# SDCARD.net
KiCad netlist of a schematic drawn in Altium Designer
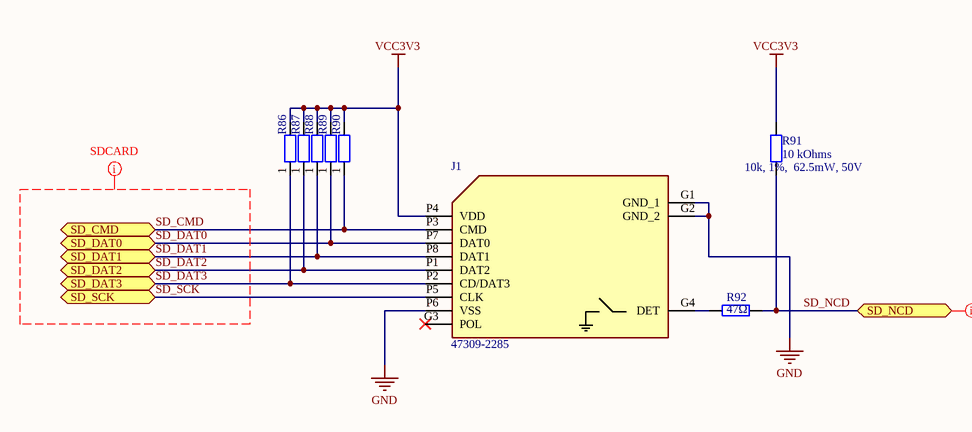
[diagram p0: SDCARD.SchDoc]

(export (version "E")
  (design (tool "Eeschema 10.0.6"))
  (components
    (comp (ref "J1")
      (value "47309-2285")
      (footprint "PCB1:473092285")
      (description "1.10mm Pitch microSD Card Header with Detect Pin Height 2.85mm Lead-Free Gold (Au) Plated 0.762")
      (fields (field (name "MOUSER PART NUMBER") "538-47309-2285") (field (name "MANUFACTURER") "Molex"))
      (libsource (lib "HamedLib") (part "47309-2285"))
    )
    (comp (ref "R86")
      (value "100 kOhms")
      (footprint "RES0402i")
      (description "0402, 100k, 1%, 62.5mW, 50V")
      (fields (field (name "PART NUMBER") "CR0402-FX-1003GLF") (field (name "VOLTAGE") "50 V"))
      (libsource (lib "AmpherLib") (part "Res_100K_1%_0402"))
    )
    (comp (ref "R87")
      (value "100 kOhms")
      (footprint "RES0402i")
      (description "0402, 100k, 1%, 62.5mW, 50V")
      (fields (field (name "PART NUMBER") "CR0402-FX-1003GLF") (field (name "VOLTAGE") "50 V"))
      (libsource (lib "AmpherLib") (part "Res_100K_1%_0402"))
    )
    (comp (ref "R88")
      (value "100 kOhms")
      (footprint "RES0402i")
      (description "0402, 100k, 1%, 62.5mW, 50V")
      (fields (field (name "PART NUMBER") "CR0402-FX-1003GLF") (field (name "VOLTAGE") "50 V"))
      (libsource (lib "AmpherLib") (part "Res_100K_1%_0402"))
    )
    (comp (ref "R89")
      (value "100 kOhms")
      (footprint "RES0402i")
      (description "0402, 100k, 1%, 62.5mW, 50V")
      (fields (field (name "PART NUMBER") "CR0402-FX-1003GLF") (field (name "VOLTAGE") "50 V"))
      (libsource (lib "AmpherLib") (part "Res_100K_1%_0402"))
    )
    (comp (ref "R90")
      (value "100 kOhms")
      (footprint "RES0402i")
      (description "0402, 100k, 1%, 62.5mW, 50V")
      (fields (field (name "PART NUMBER") "CR0402-FX-1003GLF") (field (name "VOLTAGE") "50 V"))
      (libsource (lib "AmpherLib") (part "Res_100K_1%_0402"))
    )
    (comp (ref "R91")
      (value "10 kOhms")
      (footprint "RES0402i")
      (description "0402, 10K 1%,  62.5mW, 50V")
      (fields
        (field (name "PART NUMBER") "CR0402-FX-1002GLF")
        (field (name "VOLTAGE") "50V")
        (field (name "ALTIUM_VALUE") "10k, 1%,  62.5mW, 50V")
      )
      (libsource (lib "AmpherLib") (part "Res_10k_1%_0402"))
    )
    (comp (ref "R92")
      (value "47Ω")
      (footprint "0805_R")
      (description "贴片电阻")
      (libsource (lib "RES") (part "0805 47Ω (47R0) 1%"))
    )
  )
  (nets
    (net (code "1") (name "/SD_CMD") (class "Default")
      (node (ref "J1") (pin "P3") (pinfunction "CMD_P3") (pintype "passive"))
      (node (ref "R90") (pin "1") (pinfunction "1_1") (pintype "passive"))
    )
    (net (code "2") (name "/SD_DAT0") (class "Default")
      (node (ref "J1") (pin "P7") (pinfunction "DAT0_P7") (pintype "passive"))
      (node (ref "R89") (pin "1") (pinfunction "1_1") (pintype "passive"))
    )
    (net (code "3") (name "/SD_DAT1") (class "Default")
      (node (ref "J1") (pin "P8") (pinfunction "DAT1_P8") (pintype "passive"))
      (node (ref "R88") (pin "1") (pinfunction "1_1") (pintype "passive"))
    )
    (net (code "4") (name "/SD_DAT2") (class "Default")
      (node (ref "J1") (pin "P1") (pinfunction "DAT2_P1") (pintype "passive"))
      (node (ref "R87") (pin "1") (pinfunction "1_1") (pintype "passive"))
    )
    (net (code "5") (name "/SD_DAT3") (class "Default")
      (node (ref "J1") (pin "P2") (pinfunction "CD/DAT3_P2") (pintype "passive"))
      (node (ref "R86") (pin "1") (pinfunction "1_1") (pintype "passive"))
    )
    (net (code "6") (name "/SD_NCD") (class "Default")
      (node (ref "R91") (pin "1") (pinfunction "1_1") (pintype "passive"))
      (node (ref "R92") (pin "2") (pinfunction "2_2") (pintype "passive"))
    )
    (net (code "7") (name "/SD_SCK") (class "Default")
      (node (ref "J1") (pin "P5") (pinfunction "CLK_P5") (pintype "passive"))
    )
    (net (code "8") (name "GND") (class "Default")
      (node (ref "J1") (pin "G1") (pinfunction "GND_1_G1") (pintype "passive"))
      (node (ref "J1") (pin "G2") (pinfunction "GND_2_G2") (pintype "passive"))
      (node (ref "J1") (pin "P6") (pinfunction "VSS_P6") (pintype "passive"))
    )
    (net (code "9") (name "Net-(J1-DET)") (class "Default")
      (node (ref "J1") (pin "G4") (pinfunction "DET_G4") (pintype "passive"))
      (node (ref "R92") (pin "1") (pinfunction "1_1") (pintype "passive"))
    )
    (net (code "10") (name "VCC3V3") (class "Default")
      (node (ref "J1") (pin "P4") (pinfunction "VDD_P4") (pintype "passive"))
      (node (ref "R86") (pin "2") (pinfunction "2_2") (pintype "passive"))
      (node (ref "R87") (pin "2") (pinfunction "2_2") (pintype "passive"))
      (node (ref "R88") (pin "2") (pinfunction "2_2") (pintype "passive"))
      (node (ref "R89") (pin "2") (pinfunction "2_2") (pintype "passive"))
      (node (ref "R90") (pin "2") (pinfunction "2_2") (pintype "passive"))
      (node (ref "R91") (pin "2") (pinfunction "2_2") (pintype "passive"))
    )
    (net (code "11") (name "unconnected-(J1-POL-PadG3)") (class "Default")
      (node (ref "J1") (pin "G3") (pinfunction "POL_G3") (pintype "passive+no_connect"))
    )
  )
)
